# Battery_Characterizer.net
KiCad netlist of a schematic drawn in EAGLE
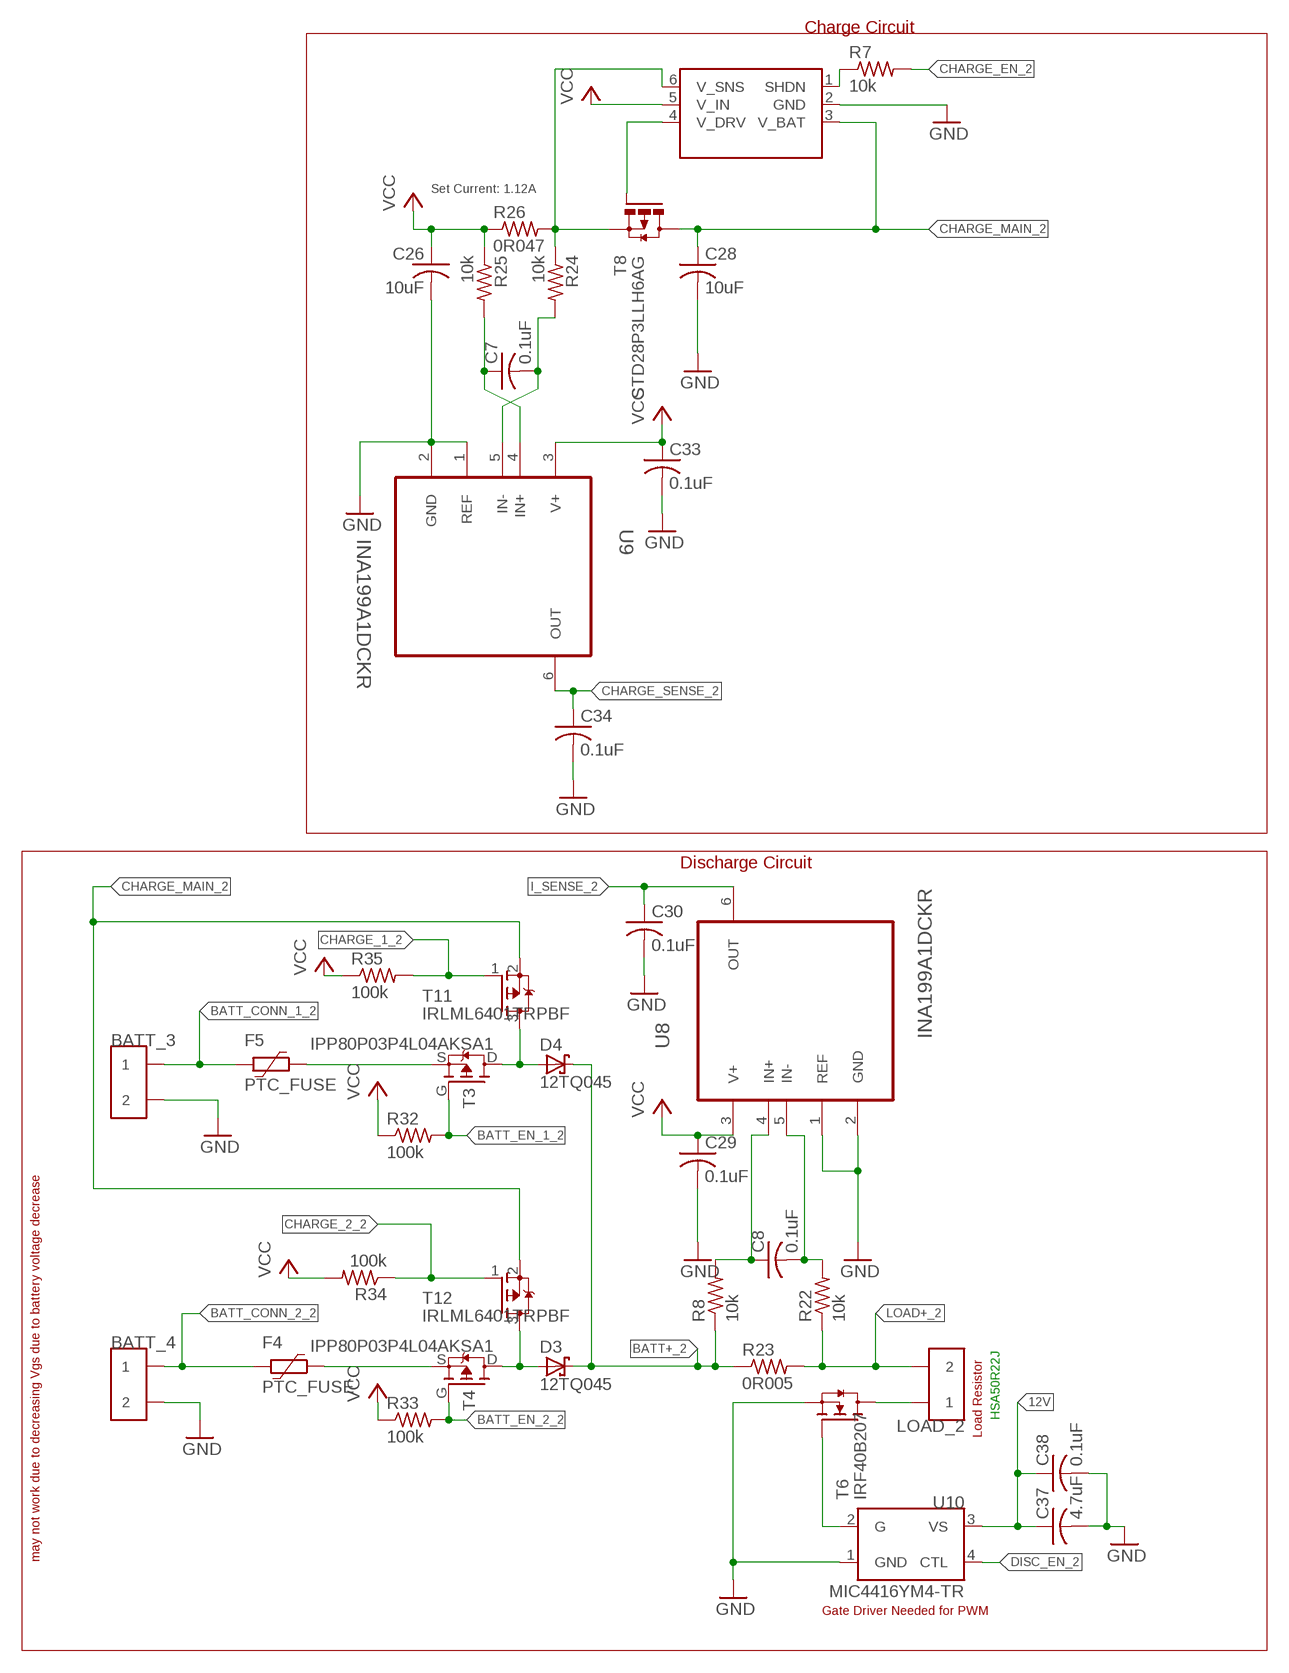
[diagram p0: schematic, sheet 1, part 1 of 2]
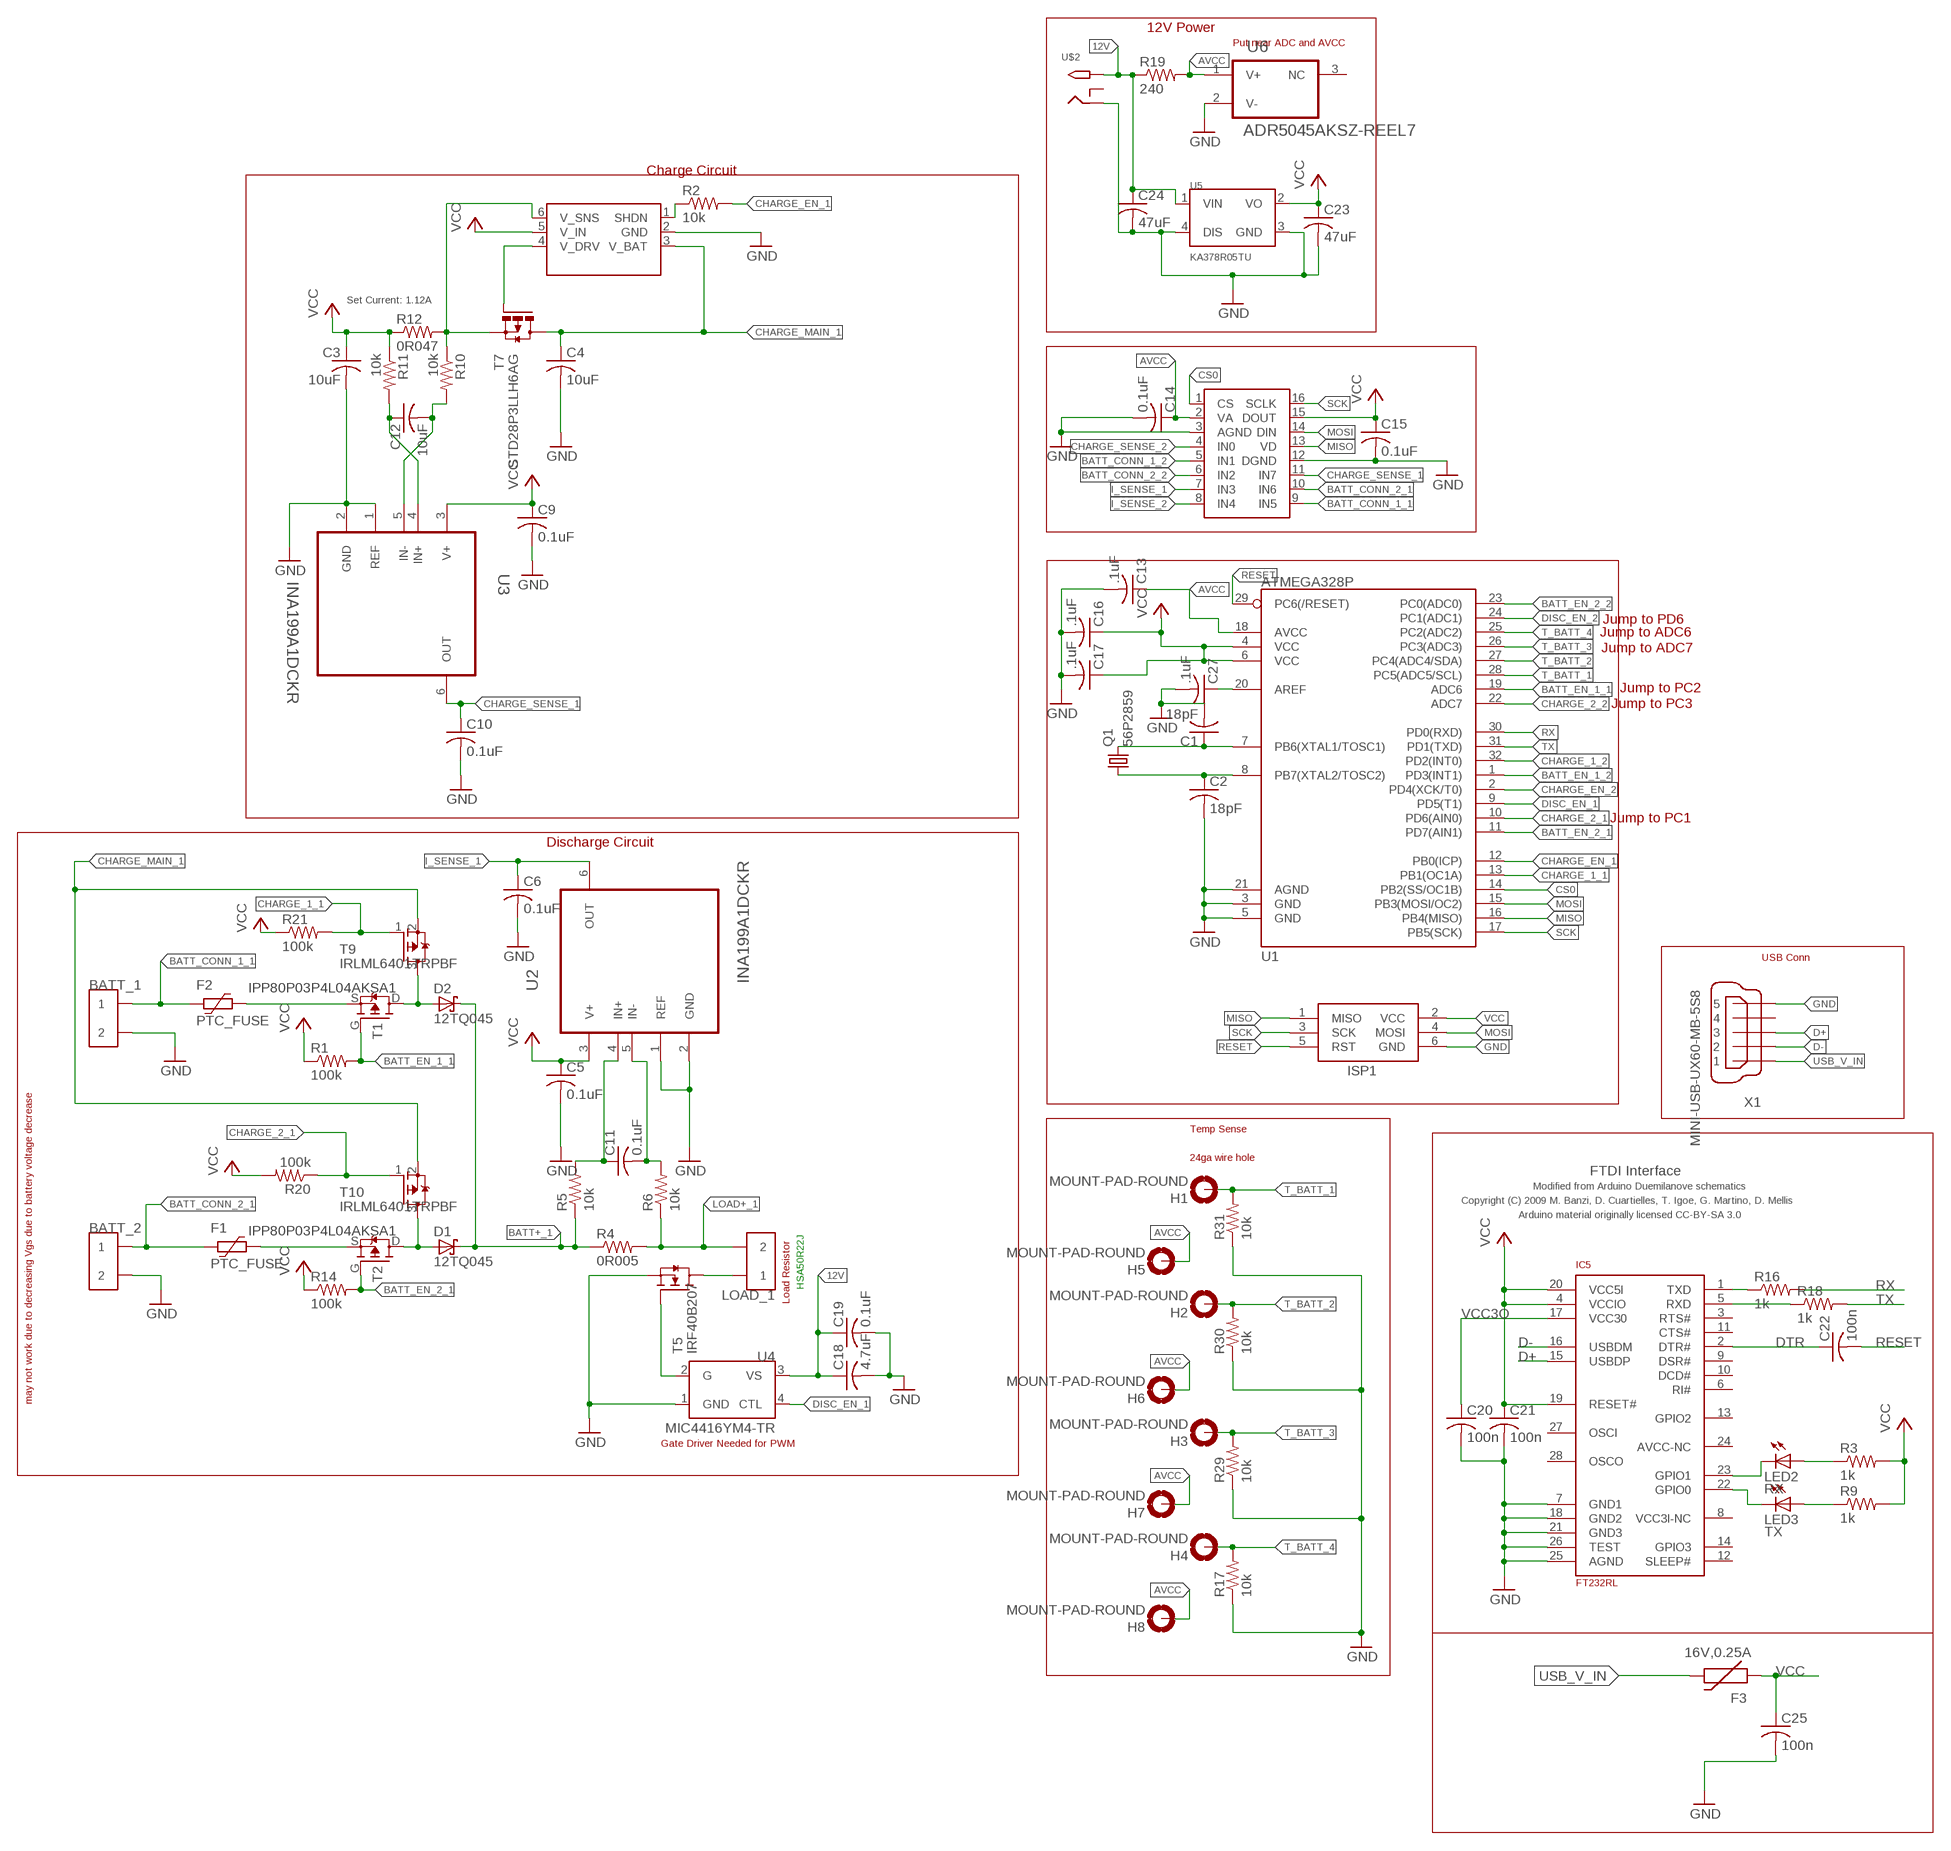
[diagram p1: schematic, sheet 1, part 2 of 2]

(export (version "E")
  (design (tool "Eeschema 10.0.6"))
  (components
    (comp (ref "BATT_1")
      (value "CONN_2")
      (footprint "eagle-import:CONNECTOR_2")
      (libsource (lib "eagle-import") (part "CONN_2"))
    )
    (comp (ref "BATT_2")
      (value "CONN_2")
      (footprint "eagle-import:CONNECTOR_2")
      (libsource (lib "eagle-import") (part "CONN_2"))
    )
    (comp (ref "BATT_3")
      (value "CONN_2")
      (footprint "eagle-import:CONNECTOR_2")
      (libsource (lib "eagle-import") (part "CONN_2"))
    )
    (comp (ref "BATT_4")
      (value "CONN_2")
      (footprint "eagle-import:CONNECTOR_2")
      (libsource (lib "eagle-import") (part "CONN_2"))
    )
    (comp (ref "C1")
      (value "18pF")
      (footprint "eagle-import:C0805")
      (libsource (lib "eagle-import") (part "C-USC0805"))
    )
    (comp (ref "C2")
      (value "18pF")
      (footprint "eagle-import:C0805")
      (libsource (lib "eagle-import") (part "C-USC0805"))
    )
    (comp (ref "C3")
      (value "10uF")
      (footprint "eagle-import:C0603")
      (libsource (lib "eagle-import") (part "C-USC0603"))
    )
    (comp (ref "C4")
      (value "10uF")
      (footprint "eagle-import:C0603")
      (libsource (lib "eagle-import") (part "C-USC0603"))
    )
    (comp (ref "C5")
      (value "0.1uF")
      (footprint "eagle-import:C0603")
      (libsource (lib "eagle-import") (part "C-USC0603"))
    )
    (comp (ref "C6")
      (value "0.1uF")
      (footprint "eagle-import:C0603")
      (libsource (lib "eagle-import") (part "C-USC0603"))
    )
    (comp (ref "C7")
      (value "0.1uF")
      (footprint "eagle-import:C0603")
      (libsource (lib "eagle-import") (part "C-USC0603"))
    )
    (comp (ref "C8")
      (value "0.1uF")
      (footprint "eagle-import:C0603")
      (libsource (lib "eagle-import") (part "C-USC0603"))
    )
    (comp (ref "C9")
      (value "0.1uF")
      (footprint "eagle-import:C0603")
      (libsource (lib "eagle-import") (part "C-USC0603"))
    )
    (comp (ref "C10")
      (value "0.1uF")
      (footprint "eagle-import:C0603")
      (libsource (lib "eagle-import") (part "C-USC0603"))
    )
    (comp (ref "C11")
      (value "0.1uF")
      (footprint "eagle-import:C0603")
      (libsource (lib "eagle-import") (part "C-USC0603"))
    )
    (comp (ref "C12")
      (value "10uF")
      (footprint "eagle-import:C0603")
      (libsource (lib "eagle-import") (part "C-USC0603"))
    )
    (comp (ref "C13")
      (value ".1uF")
      (footprint "eagle-import:C0603")
      (libsource (lib "eagle-import") (part "C-USC0603"))
    )
    (comp (ref "C14")
      (value "0.1uF")
      (footprint "eagle-import:C0603")
      (libsource (lib "eagle-import") (part "C-USC0603"))
    )
    (comp (ref "C15")
      (value "0.1uF")
      (footprint "eagle-import:C0603")
      (libsource (lib "eagle-import") (part "C-USC0603"))
    )
    (comp (ref "C16")
      (value ".1uF")
      (footprint "eagle-import:C0603")
      (libsource (lib "eagle-import") (part "C-USC0603"))
    )
    (comp (ref "C17")
      (value ".1uF")
      (footprint "eagle-import:C0603")
      (libsource (lib "eagle-import") (part "C-USC0603"))
    )
    (comp (ref "C18")
      (value "4.7uF")
      (footprint "eagle-import:C0805")
      (libsource (lib "eagle-import") (part "C-USC0805"))
    )
    (comp (ref "C19")
      (value "0.1uF")
      (footprint "eagle-import:C0603")
      (libsource (lib "eagle-import") (part "C-USC0603"))
    )
    (comp (ref "C20")
      (value "100n")
      (footprint "eagle-import:C0805")
      (libsource (lib "eagle-import") (part "C-USC0805"))
    )
    (comp (ref "C21")
      (value "100n")
      (footprint "eagle-import:C0805")
      (libsource (lib "eagle-import") (part "C-USC0805"))
    )
    (comp (ref "C22")
      (value "100n")
      (footprint "eagle-import:C0805")
      (libsource (lib "eagle-import") (part "C-USC0805"))
    )
    (comp (ref "C23")
      (value "47uF")
      (footprint "eagle-import:C0805")
      (libsource (lib "eagle-import") (part "resistor_C-USC0805"))
    )
    (comp (ref "C24")
      (value "47uF")
      (footprint "eagle-import:C0805")
      (libsource (lib "eagle-import") (part "C-USC0805"))
    )
    (comp (ref "C25")
      (value "100n")
      (footprint "eagle-import:C0805")
      (libsource (lib "eagle-import") (part "C-USC0805"))
    )
    (comp (ref "C26")
      (value "10uF")
      (footprint "eagle-import:C0603")
      (libsource (lib "eagle-import") (part "C-USC0603"))
    )
    (comp (ref "C27")
      (value ".1uF")
      (footprint "eagle-import:C0603")
      (libsource (lib "eagle-import") (part "C-USC0603"))
    )
    (comp (ref "C28")
      (value "10uF")
      (footprint "eagle-import:C0603")
      (libsource (lib "eagle-import") (part "C-USC0603"))
    )
    (comp (ref "C29")
      (value "0.1uF")
      (footprint "eagle-import:C0603")
      (libsource (lib "eagle-import") (part "C-USC0603"))
    )
    (comp (ref "C30")
      (value "0.1uF")
      (footprint "eagle-import:C0603")
      (libsource (lib "eagle-import") (part "C-USC0603"))
    )
    (comp (ref "C33")
      (value "0.1uF")
      (footprint "eagle-import:C0603")
      (libsource (lib "eagle-import") (part "C-USC0603"))
    )
    (comp (ref "C34")
      (value "0.1uF")
      (footprint "eagle-import:C0603")
      (libsource (lib "eagle-import") (part "C-USC0603"))
    )
    (comp (ref "C37")
      (value "4.7uF")
      (footprint "eagle-import:C0805")
      (libsource (lib "eagle-import") (part "C-USC0805"))
    )
    (comp (ref "C38")
      (value "0.1uF")
      (footprint "eagle-import:C0603")
      (libsource (lib "eagle-import") (part "C-USC0603"))
    )
    (comp (ref "D1")
      (value "12TQ045")
      (footprint "eagle-import:TO220-2")
      (libsource (lib "eagle-import") (part "12TQ045"))
    )
    (comp (ref "D2")
      (value "12TQ045")
      (footprint "eagle-import:TO220-2")
      (libsource (lib "eagle-import") (part "12TQ045"))
    )
    (comp (ref "D3")
      (value "12TQ045")
      (footprint "eagle-import:TO220-2")
      (libsource (lib "eagle-import") (part "12TQ045"))
    )
    (comp (ref "D4")
      (value "12TQ045")
      (footprint "eagle-import:TO220-2")
      (libsource (lib "eagle-import") (part "12TQ045"))
    )
    (comp (ref "F1")
      (value "PTC_FUSE")
      (footprint "eagle-import:RGEF1100")
      (libsource (lib "eagle-import") (part "PTC_FUSE"))
    )
    (comp (ref "F2")
      (value "PTC_FUSE")
      (footprint "eagle-import:RGEF1100")
      (libsource (lib "eagle-import") (part "PTC_FUSE"))
    )
    (comp (ref "F3")
      (value "16V,0.25A")
      (footprint "eagle-import:PTC-1206")
      (libsource (lib "eagle-import") (part "PTCSMD"))
    )
    (comp (ref "F4")
      (value "PTC_FUSE")
      (footprint "eagle-import:RGEF1100")
      (libsource (lib "eagle-import") (part "PTC_FUSE"))
    )
    (comp (ref "F5")
      (value "PTC_FUSE")
      (footprint "eagle-import:RGEF1100")
      (libsource (lib "eagle-import") (part "PTC_FUSE"))
    )
    (comp (ref "H1")
      (value "MOUNT-PAD-ROUND")
      (footprint "eagle-import:032-PAD")
      (libsource (lib "eagle-import") (part "MOUNT-PAD-ROUND"))
    )
    (comp (ref "H2")
      (value "MOUNT-PAD-ROUND")
      (footprint "eagle-import:032-PAD")
      (libsource (lib "eagle-import") (part "MOUNT-PAD-ROUND"))
    )
    (comp (ref "H3")
      (value "MOUNT-PAD-ROUND")
      (footprint "eagle-import:032-PAD")
      (libsource (lib "eagle-import") (part "MOUNT-PAD-ROUND"))
    )
    (comp (ref "H4")
      (value "MOUNT-PAD-ROUND")
      (footprint "eagle-import:032-PAD")
      (libsource (lib "eagle-import") (part "MOUNT-PAD-ROUND"))
    )
    (comp (ref "H5")
      (value "MOUNT-PAD-ROUND")
      (footprint "eagle-import:032-PAD")
      (libsource (lib "eagle-import") (part "MOUNT-PAD-ROUND"))
    )
    (comp (ref "H6")
      (value "MOUNT-PAD-ROUND")
      (footprint "eagle-import:032-PAD")
      (libsource (lib "eagle-import") (part "MOUNT-PAD-ROUND"))
    )
    (comp (ref "H7")
      (value "MOUNT-PAD-ROUND")
      (footprint "eagle-import:032-PAD")
      (libsource (lib "eagle-import") (part "MOUNT-PAD-ROUND"))
    )
    (comp (ref "H8")
      (value "MOUNT-PAD-ROUND")
      (footprint "eagle-import:032-PAD")
      (libsource (lib "eagle-import") (part "MOUNT-PAD-ROUND"))
    )
    (comp (ref "IC5")
      (value "FT232RL")
      (footprint "eagle-import:SSOP28")
      (libsource (lib "eagle-import") (part "FT232RL"))
    )
    (comp (ref "ISP1")
      (value "AVRISP-6")
      (footprint "eagle-import:AVRISP")
      (libsource (lib "eagle-import") (part "AVRISP-6"))
    )
    (comp (ref "LED2")
      (value "RX")
      (footprint "eagle-import:CHIPLED_0805")
      (libsource (lib "eagle-import") (part "LEDCHIPLED_0805"))
    )
    (comp (ref "LED3")
      (value "TX")
      (footprint "eagle-import:CHIPLED_0805")
      (libsource (lib "eagle-import") (part "LEDCHIPLED_0805"))
    )
    (comp (ref "LOAD_1")
      (value "CONN_2")
      (footprint "eagle-import:CONNECTOR_2")
      (libsource (lib "eagle-import") (part "CONN_2"))
    )
    (comp (ref "LOAD_2")
      (value "CONN_2")
      (footprint "eagle-import:CONNECTOR_2")
      (libsource (lib "eagle-import") (part "CONN_2"))
    )
    (comp (ref "PC1")
      (value "MCP73826")
      (footprint "eagle-import:SOT23-6")
      (libsource (lib "eagle-import") (part "MCP73826"))
    )
    (comp (ref "PC2")
      (value "MCP73826")
      (footprint "eagle-import:SOT23-6")
      (libsource (lib "eagle-import") (part "MCP73826"))
    )
    (comp (ref "Q1")
      (value "56P2859")
      (footprint "eagle-import:HC49UP")
      (libsource (lib "eagle-import") (part "CRYSTALSMD"))
    )
    (comp (ref "R1")
      (value "100k")
      (footprint "eagle-import:M0805")
      (libsource (lib "eagle-import") (part "R-US_M0805"))
    )
    (comp (ref "R2")
      (value "10k")
      (footprint "eagle-import:R0603")
      (libsource (lib "eagle-import") (part "resistor_R-US_R0603"))
    )
    (comp (ref "R3")
      (value "1k")
      (footprint "eagle-import:R0805")
      (libsource (lib "eagle-import") (part "R-US_R0805"))
    )
    (comp (ref "R4")
      (value "0R005")
      (footprint "eagle-import:R-3637")
      (libsource (lib "eagle-import") (part "WSL3637"))
    )
    (comp (ref "R5")
      (value "10k")
      (footprint "eagle-import:R0603")
      (libsource (lib "eagle-import") (part "resistor_R-US_R0603"))
    )
    (comp (ref "R6")
      (value "10k")
      (footprint "eagle-import:R0603")
      (libsource (lib "eagle-import") (part "resistor_R-US_R0603"))
    )
    (comp (ref "R7")
      (value "10k")
      (footprint "eagle-import:R0603")
      (libsource (lib "eagle-import") (part "resistor_R-US_R0603"))
    )
    (comp (ref "R8")
      (value "10k")
      (footprint "eagle-import:R0603")
      (libsource (lib "eagle-import") (part "resistor_R-US_R0603"))
    )
    (comp (ref "R9")
      (value "1k")
      (footprint "eagle-import:R0805")
      (libsource (lib "eagle-import") (part "R-US_R0805"))
    )
    (comp (ref "R10")
      (value "10k")
      (footprint "eagle-import:R0603")
      (libsource (lib "eagle-import") (part "resistor_R-US_R0603"))
    )
    (comp (ref "R11")
      (value "10k")
      (footprint "eagle-import:R0603")
      (libsource (lib "eagle-import") (part "resistor_R-US_R0603"))
    )
    (comp (ref "R12")
      (value "0R047")
      (footprint "eagle-import:M1206")
      (libsource (lib "eagle-import") (part "resistor_R-US_M1206"))
    )
    (comp (ref "R14")
      (value "100k")
      (footprint "eagle-import:M0805")
      (libsource (lib "eagle-import") (part "R-US_M0805"))
    )
    (comp (ref "R16")
      (value "1k")
      (footprint "eagle-import:R0805")
      (libsource (lib "eagle-import") (part "R-US_R0805"))
    )
    (comp (ref "R17")
      (value "10k")
      (footprint "eagle-import:R0603")
      (libsource (lib "eagle-import") (part "resistor_R-US_R0603"))
    )
    (comp (ref "R18")
      (value "1k")
      (footprint "eagle-import:R0805")
      (libsource (lib "eagle-import") (part "R-US_R0805"))
    )
    (comp (ref "R19")
      (value "240")
      (footprint "eagle-import:R0603")
      (libsource (lib "eagle-import") (part "resistor_R-US_R0603"))
    )
    (comp (ref "R20")
      (value "100k")
      (footprint "eagle-import:M0805")
      (libsource (lib "eagle-import") (part "R-US_M0805"))
    )
    (comp (ref "R21")
      (value "100k")
      (footprint "eagle-import:M0805")
      (libsource (lib "eagle-import") (part "R-US_M0805"))
    )
    (comp (ref "R22")
      (value "10k")
      (footprint "eagle-import:R0603")
      (libsource (lib "eagle-import") (part "resistor_R-US_R0603"))
    )
    (comp (ref "R23")
      (value "0R005")
      (footprint "eagle-import:R-3637")
      (libsource (lib "eagle-import") (part "WSL3637"))
    )
    (comp (ref "R24")
      (value "10k")
      (footprint "eagle-import:R0603")
      (libsource (lib "eagle-import") (part "resistor_R-US_R0603"))
    )
    (comp (ref "R25")
      (value "10k")
      (footprint "eagle-import:R0603")
      (libsource (lib "eagle-import") (part "resistor_R-US_R0603"))
    )
    (comp (ref "R26")
      (value "0R047")
      (footprint "eagle-import:M1206")
      (libsource (lib "eagle-import") (part "resistor_R-US_M1206"))
    )
    (comp (ref "R29")
      (value "10k")
      (footprint "eagle-import:R0603")
      (libsource (lib "eagle-import") (part "resistor_R-US_R0603"))
    )
    (comp (ref "R30")
      (value "10k")
      (footprint "eagle-import:R0603")
      (libsource (lib "eagle-import") (part "resistor_R-US_R0603"))
    )
    (comp (ref "R31")
      (value "10k")
      (footprint "eagle-import:R0603")
      (libsource (lib "eagle-import") (part "resistor_R-US_R0603"))
    )
    (comp (ref "R32")
      (value "100k")
      (footprint "eagle-import:M0805")
      (libsource (lib "eagle-import") (part "R-US_M0805"))
    )
    (comp (ref "R33")
      (value "100k")
      (footprint "eagle-import:M0805")
      (libsource (lib "eagle-import") (part "R-US_M0805"))
    )
    (comp (ref "R34")
      (value "100k")
      (footprint "eagle-import:M0805")
      (libsource (lib "eagle-import") (part "R-US_M0805"))
    )
    (comp (ref "R35")
      (value "100k")
      (footprint "eagle-import:M0805")
      (libsource (lib "eagle-import") (part "R-US_M0805"))
    )
    (comp (ref "T1")
      (value "IPP80P03P4L04AKSA1")
      (footprint "eagle-import:TO220-3")
      (libsource (lib "eagle-import") (part "IPP80P03P4L04AKSA1"))
    )
    (comp (ref "T2")
      (value "IPP80P03P4L04AKSA1")
      (footprint "eagle-import:TO220-3")
      (libsource (lib "eagle-import") (part "IPP80P03P4L04AKSA1"))
    )
    (comp (ref "T3")
      (value "IPP80P03P4L04AKSA1")
      (footprint "eagle-import:TO220-3")
      (libsource (lib "eagle-import") (part "IPP80P03P4L04AKSA1"))
    )
    (comp (ref "T4")
      (value "IPP80P03P4L04AKSA1")
      (footprint "eagle-import:TO220-3")
      (libsource (lib "eagle-import") (part "IPP80P03P4L04AKSA1"))
    )
    (comp (ref "T5")
      (value "IRF40B207")
      (footprint "eagle-import:TO220-3")
      (libsource (lib "eagle-import") (part "IRF40B207"))
    )
    (comp (ref "T6")
      (value "IRF40B207")
      (footprint "eagle-import:TO220-3")
      (libsource (lib "eagle-import") (part "IRF40B207"))
    )
    (comp (ref "T7")
      (value "STD28P3LLH6AG")
      (footprint "eagle-import:D2-PAK")
      (libsource (lib "eagle-import") (part "STD28P3LLH6AG"))
    )
    (comp (ref "T8")
      (value "STD28P3LLH6AG")
      (footprint "eagle-import:D2-PAK")
      (libsource (lib "eagle-import") (part "STD28P3LLH6AG"))
    )
    (comp (ref "T9")
      (value "IRLML6401TRPBF")
      (footprint "eagle-import:SOT95P237X112-3N")
      (libsource (lib "eagle-import") (part "IRLML6401TRPBF"))
    )
    (comp (ref "T10")
      (value "IRLML6401TRPBF")
      (footprint "eagle-import:SOT95P237X112-3N")
      (libsource (lib "eagle-import") (part "IRLML6401TRPBF"))
    )
    (comp (ref "T11")
      (value "IRLML6401TRPBF")
      (footprint "eagle-import:SOT95P237X112-3N")
      (libsource (lib "eagle-import") (part "IRLML6401TRPBF"))
    )
    (comp (ref "T12")
      (value "IRLML6401TRPBF")
      (footprint "eagle-import:SOT95P237X112-3N")
      (libsource (lib "eagle-import") (part "IRLML6401TRPBF"))
    )
    (comp (ref "U$2")
      (value "2.1MMJACKTHM")
      (footprint "eagle-import:PJ-102A")
      (libsource (lib "eagle-import") (part "2.1MMJACKTHM"))
    )
    (comp (ref "U$7")
      (value "ADC128S022CIMTX/NOPB")
      (footprint "eagle-import:TSSOP16")
      (libsource (lib "eagle-import") (part "ADC128S022CIMTX/NOPB"))
    )
    (comp (ref "U1")
      (value "ATMEGA328P")
      (footprint "eagle-import:TQFP32-08")
      (libsource (lib "eagle-import") (part "ATMEGA328_SMT"))
    )
    (comp (ref "U2")
      (value "INA199A1DCKR")
      (footprint "eagle-import:SOT65P210X110-6N")
      (libsource (lib "eagle-import") (part "INA199A1DCKR"))
    )
    (comp (ref "U3")
      (value "INA199A1DCKR")
      (footprint "eagle-import:SOT65P210X110-6N")
      (libsource (lib "eagle-import") (part "INA199A1DCKR"))
    )
    (comp (ref "U4")
      (value "MIC4416YM4-TR")
      (footprint "eagle-import:4-SOT_143")
      (libsource (lib "eagle-import") (part "MIC4416YM4-TR"))
    )
    (comp (ref "U5")
      (value "KA378R05TU")
      (footprint "eagle-import:TO-220-4")
      (libsource (lib "eagle-import") (part "KA378R05TU"))
    )
    (comp (ref "U6")
      (value "ADR5045AKSZ-REEL7")
      (footprint "eagle-import:SOT95P237X112-3N")
      (fields (field (name "MPN") "ADR5041BRTZ-R2") (field (name "MPN_1") "ADR5045AKSZ-REEL7"))
      (libsource (lib "eagle-import") (part "ADR5041BRTZ-R2"))
    )
    (comp (ref "U8")
      (value "INA199A1DCKR")
      (footprint "eagle-import:SOT65P210X110-6N")
      (libsource (lib "eagle-import") (part "INA199A1DCKR"))
    )
    (comp (ref "U9")
      (value "INA199A1DCKR")
      (footprint "eagle-import:SOT65P210X110-6N")
      (libsource (lib "eagle-import") (part "INA199A1DCKR"))
    )
    (comp (ref "U10")
      (value "MIC4416YM4-TR")
      (footprint "eagle-import:4-SOT_143")
      (libsource (lib "eagle-import") (part "MIC4416YM4-TR"))
    )
    (comp (ref "X1")
      (value "MINI-USB-UX60-MB-5S8")
      (footprint "eagle-import:UX60-MB-5S8")
      (libsource (lib "eagle-import") (part "MINI-USB-UX60-MB-5S8"))
    )
  )
  (nets
    (net (code "1") (name "/DTR") (class "Default")
      (node (ref "C22") (pin "1") (pinfunction "1_1") (pintype "passive"))
      (node (ref "IC5") (pin "2") (pinfunction "DTR#_2") (pintype "output"))
    )
    (net (code "2") (name "/VCC3O") (class "Default")
      (node (ref "C20") (pin "1") (pinfunction "1_1") (pintype "passive"))
      (node (ref "IC5") (pin "17") (pinfunction "VCC30_17") (pintype "power_in"))
    )
    (net (code "3") (name "12V") (class "Default")
      (node (ref "C18") (pin "1") (pinfunction "1_1") (pintype "passive"))
      (node (ref "C19") (pin "1") (pinfunction "1_1") (pintype "passive"))
      (node (ref "C24") (pin "1") (pinfunction "1_1") (pintype "passive"))
      (node (ref "C37") (pin "1") (pinfunction "1_1") (pintype "passive"))
      (node (ref "C38") (pin "1") (pinfunction "1_1") (pintype "passive"))
      (node (ref "R19") (pin "1") (pinfunction "1_1") (pintype "passive"))
      (node (ref "U$2") (pin "TIP") (pinfunction "TIP_TIP") (pintype "bidirectional"))
      (node (ref "U10") (pin "3") (pinfunction "VS_3") (pintype "bidirectional"))
      (node (ref "U4") (pin "3") (pinfunction "VS_3") (pintype "bidirectional"))
      (node (ref "U5") (pin "1") (pinfunction "VIN_1") (pintype "bidirectional"))
    )
    (net (code "4") (name "AVCC") (class "Default")
      (node (ref "C13") (pin "1") (pinfunction "1_1") (pintype "passive"))
      (node (ref "C14") (pin "1") (pinfunction "1_1") (pintype "passive"))
      (node (ref "H5") (pin "1") (pinfunction "MOUNT_1") (pintype "passive"))
      (node (ref "H6") (pin "1") (pinfunction "MOUNT_1") (pintype "passive"))
      (node (ref "H7") (pin "1") (pinfunction "MOUNT_1") (pintype "passive"))
      (node (ref "H8") (pin "1") (pinfunction "MOUNT_1") (pintype "passive"))
      (node (ref "R19") (pin "2") (pinfunction "2_2") (pintype "passive"))
      (node (ref "U$7") (pin "2") (pinfunction "VA_2") (pintype "bidirectional"))
      (node (ref "U1") (pin "18") (pinfunction "AVCC_18") (pintype "bidirectional"))
      (node (ref "U6") (pin "1") (pinfunction "V+_1") (pintype "power_in"))
    )
    (net (code "5") (name "BATT+_1") (class "Default")
      (node (ref "D1") (pin "C") (pinfunction "C_C") (pintype "passive"))
      (node (ref "D2") (pin "C") (pinfunction "C_C") (pintype "passive"))
      (node (ref "R4") (pin "1") (pinfunction "1_1") (pintype "passive"))
      (node (ref "R4") (pin "2") (pinfunction "1_2") (pintype "passive"))
      (node (ref "R5") (pin "1") (pinfunction "1_1") (pintype "passive"))
    )
    (net (code "6") (name "BATT+_2") (class "Default")
      (node (ref "D3") (pin "C") (pinfunction "C_C") (pintype "passive"))
      (node (ref "D4") (pin "C") (pinfunction "C_C") (pintype "passive"))
      (node (ref "R23") (pin "1") (pinfunction "1_1") (pintype "passive"))
      (node (ref "R23") (pin "2") (pinfunction "1_2") (pintype "passive"))
      (node (ref "R8") (pin "1") (pinfunction "1_1") (pintype "passive"))
    )
    (net (code "7") (name "BATT_CONN_1_1") (class "Default")
      (node (ref "BATT_1") (pin "1") (pinfunction "1_1") (pintype "bidirectional"))
      (node (ref "BATT_1") (pin "2") (pinfunction "1_2") (pintype "bidirectional"))
      (node (ref "F2") (pin "P$2") (pinfunction "2_P$2") (pintype "passive"))
      (node (ref "U$7") (pin "9") (pinfunction "IN5_9") (pintype "bidirectional"))
    )
    (net (code "8") (name "BATT_CONN_1_2") (class "Default")
      (node (ref "BATT_3") (pin "1") (pinfunction "1_1") (pintype "bidirectional"))
      (node (ref "BATT_3") (pin "2") (pinfunction "1_2") (pintype "bidirectional"))
      (node (ref "F5") (pin "P$2") (pinfunction "2_P$2") (pintype "passive"))
      (node (ref "U$7") (pin "5") (pinfunction "IN1_5") (pintype "bidirectional"))
    )
    (net (code "9") (name "BATT_CONN_2_1") (class "Default")
      (node (ref "BATT_2") (pin "1") (pinfunction "1_1") (pintype "bidirectional"))
      (node (ref "BATT_2") (pin "2") (pinfunction "1_2") (pintype "bidirectional"))
      (node (ref "F1") (pin "P$2") (pinfunction "2_P$2") (pintype "passive"))
      (node (ref "U$7") (pin "10") (pinfunction "IN6_10") (pintype "bidirectional"))
    )
    (net (code "10") (name "BATT_CONN_2_2") (class "Default")
      (node (ref "BATT_4") (pin "1") (pinfunction "1_1") (pintype "bidirectional"))
      (node (ref "BATT_4") (pin "2") (pinfunction "1_2") (pintype "bidirectional"))
      (node (ref "F4") (pin "P$2") (pinfunction "2_P$2") (pintype "passive"))
      (node (ref "U$7") (pin "6") (pinfunction "IN2_6") (pintype "bidirectional"))
    )
    (net (code "11") (name "BATT_EN_1_1") (class "Default")
      (node (ref "R1") (pin "2") (pinfunction "2_2") (pintype "passive"))
      (node (ref "T1") (pin "G") (pinfunction "G_G") (pintype "passive"))
      (node (ref "U1") (pin "19") (pinfunction "ADC6_19") (pintype "bidirectional"))
    )
    (net (code "12") (name "BATT_EN_1_2") (class "Default")
      (node (ref "R32") (pin "2") (pinfunction "2_2") (pintype "passive"))
      (node (ref "T3") (pin "G") (pinfunction "G_G") (pintype "passive"))
      (node (ref "U1") (pin "1") (pinfunction "PD3(INT1)_1") (pintype "bidirectional"))
    )
    (net (code "13") (name "BATT_EN_2_1") (class "Default")
      (node (ref "R14") (pin "2") (pinfunction "2_2") (pintype "passive"))
      (node (ref "T2") (pin "G") (pinfunction "G_G") (pintype "passive"))
      (node (ref "U1") (pin "11") (pinfunction "PD7(AIN1)_11") (pintype "bidirectional"))
    )
    (net (code "14") (name "BATT_EN_2_2") (class "Default")
      (node (ref "R33") (pin "2") (pinfunction "2_2") (pintype "passive"))
      (node (ref "T4") (pin "G") (pinfunction "G_G") (pintype "passive"))
      (node (ref "U1") (pin "23") (pinfunction "PC0(ADC0)_23") (pintype "bidirectional"))
    )
    (net (code "15") (name "CHARGE_1_1") (class "Default")
      (node (ref "R21") (pin "2") (pinfunction "2_2") (pintype "passive"))
      (node (ref "T9") (pin "1") (pinfunction "G_1") (pintype "passive"))
      (node (ref "U1") (pin "13") (pinfunction "PB1(OC1A)_13") (pintype "bidirectional"))
    )
    (net (code "16") (name "CHARGE_1_2") (class "Default")
      (node (ref "R35") (pin "2") (pinfunction "2_2") (pintype "passive"))
      (node (ref "T11") (pin "1") (pinfunction "G_1") (pintype "passive"))
      (node (ref "U1") (pin "32") (pinfunction "PD2(INT0)_32") (pintype "bidirectional"))
    )
    (net (code "17") (name "CHARGE_2_1") (class "Default")
      (node (ref "R20") (pin "1") (pinfunction "1_1") (pintype "passive"))
      (node (ref "T10") (pin "1") (pinfunction "G_1") (pintype "passive"))
      (node (ref "U1") (pin "10") (pinfunction "PD6(AIN0)_10") (pintype "bidirectional"))
    )
    (net (code "18") (name "CHARGE_2_2") (class "Default")
      (node (ref "R34") (pin "1") (pinfunction "1_1") (pintype "passive"))
      (node (ref "T12") (pin "1") (pinfunction "G_1") (pintype "passive"))
      (node (ref "U1") (pin "22") (pinfunction "ADC7_22") (pintype "bidirectional"))
    )
    (net (code "19") (name "CHARGE_EN_1") (class "Default")
      (node (ref "R2") (pin "2") (pinfunction "2_2") (pintype "passive"))
      (node (ref "U1") (pin "12") (pinfunction "PB0(ICP)_12") (pintype "bidirectional"))
    )
    (net (code "20") (name "CHARGE_EN_2") (class "Default")
      (node (ref "R7") (pin "2") (pinfunction "2_2") (pintype "passive"))
      (node (ref "U1") (pin "2") (pinfunction "PD4(XCK/T0)_2") (pintype "bidirectional"))
    )
    (net (code "21") (name "CHARGE_MAIN_1") (class "Default")
      (node (ref "C4") (pin "1") (pinfunction "1_1") (pintype "passive"))
      (node (ref "PC1") (pin "3") (pinfunction "V_BAT_3") (pintype "bidirectional"))
      (node (ref "T10") (pin "2") (pinfunction "S_2") (pintype "passive"))
      (node (ref "T7") (pin "2") (pinfunction "D_2") (pintype "passive"))
      (node (ref "T7") (pin "P$1") (pinfunction "D_P$1") (pintype "passive"))
      (node (ref "T7") (pin "P$10") (pinfunction "D_P$10") (pintype "passive"))
      (node (ref "T7") (pin "P$11") (pinfunction "D_P$11") (pintype "passive"))
      (node (ref "T7") (pin "P$12") (pinfunction "D_P$12") (pintype "passive"))
      (node (ref "T7") (pin "P$13") (pinfunction "D_P$13") (pintype "passive"))
      (node (ref "T7") (pin "P$14") (pinfunction "D_P$14") (pintype "passive"))
      (node (ref "T7") (pin "P$15") (pinfunction "D_P$15") (pintype "passive"))
      (node (ref "T7") (pin "P$16") (pinfunction "D_P$16") (pintype "passive"))
      (node (ref "T7") (pin "P$17") (pinfunction "D_P$17") (pintype "passive"))
      (node (ref "T7") (pin "P$18") (pinfunction "D_P$18") (pintype "passive"))
      (node (ref "T7") (pin "P$19") (pinfunction "D_P$19") (pintype "passive"))
      (node (ref "T7") (pin "P$2") (pinfunction "D_P$2") (pintype "passive"))
      (node (ref "T7") (pin "P$20") (pinfunction "D_P$20") (pintype "passive"))
      (node (ref "T7") (pin "P$21") (pinfunction "D_P$21") (pintype "passive"))
      (node (ref "T7") (pin "P$22") (pinfunction "D_P$22") (pintype "passive"))
      (node (ref "T7") (pin "P$23") (pinfunction "D_P$23") (pintype "passive"))
      (node (ref "T7") (pin "P$24") (pinfunction "D_P$24") (pintype "passive"))
      (node (ref "T7") (pin "P$25") (pinfunction "D_P$25") (pintype "passive"))
      (node (ref "T7") (pin "P$26") (pinfunction "D_P$26") (pintype "passive"))
      (node (ref "T7") (pin "P$27") (pinfunction "D_P$27") (pintype "passive"))
      (node (ref "T7") (pin "P$28") (pinfunction "D_P$28") (pintype "passive"))
      (node (ref "T7") (pin "P$29") (pinfunction "D_P$29") (pintype "passive"))
      (node (ref "T7") (pin "P$3") (pinfunction "D_P$3") (pintype "passive"))
      (node (ref "T7") (pin "P$30") (pinfunction "D_P$30") (pintype "passive"))
      (node (ref "T7") (pin "P$4") (pinfunction "D_P$4") (pintype "passive"))
      (node (ref "T7") (pin "P$5") (pinfunction "D_P$5") (pintype "passive"))
      (node (ref "T7") (pin "P$6") (pinfunction "D_P$6") (pintype "passive"))
      (node (ref "T7") (pin "P$7") (pinfunction "D_P$7") (pintype "passive"))
      (node (ref "T7") (pin "P$8") (pinfunction "D_P$8") (pintype "passive"))
      (node (ref "T7") (pin "P$9") (pinfunction "D_P$9") (pintype "passive"))
      (node (ref "T9") (pin "2") (pinfunction "S_2") (pintype "passive"))
    )
    (net (code "22") (name "CHARGE_MAIN_2") (class "Default")
      (node (ref "C28") (pin "1") (pinfunction "1_1") (pintype "passive"))
      (node (ref "PC2") (pin "3") (pinfunction "V_BAT_3") (pintype "bidirectional"))
      (node (ref "T11") (pin "2") (pinfunction "S_2") (pintype "passive"))
      (node (ref "T12") (pin "2") (pinfunction "S_2") (pintype "passive"))
      (node (ref "T8") (pin "2") (pinfunction "D_2") (pintype "passive"))
      (node (ref "T8") (pin "P$1") (pinfunction "D_P$1") (pintype "passive"))
      (node (ref "T8") (pin "P$10") (pinfunction "D_P$10") (pintype "passive"))
      (node (ref "T8") (pin "P$11") (pinfunction "D_P$11") (pintype "passive"))
      (node (ref "T8") (pin "P$12") (pinfunction "D_P$12") (pintype "passive"))
      (node (ref "T8") (pin "P$13") (pinfunction "D_P$13") (pintype "passive"))
      (node (ref "T8") (pin "P$14") (pinfunction "D_P$14") (pintype "passive"))
      (node (ref "T8") (pin "P$15") (pinfunction "D_P$15") (pintype "passive"))
      (node (ref "T8") (pin "P$16") (pinfunction "D_P$16") (pintype "passive"))
      (node (ref "T8") (pin "P$17") (pinfunction "D_P$17") (pintype "passive"))
      (node (ref "T8") (pin "P$18") (pinfunction "D_P$18") (pintype "passive"))
      (node (ref "T8") (pin "P$19") (pinfunction "D_P$19") (pintype "passive"))
      (node (ref "T8") (pin "P$2") (pinfunction "D_P$2") (pintype "passive"))
      (node (ref "T8") (pin "P$20") (pinfunction "D_P$20") (pintype "passive"))
      (node (ref "T8") (pin "P$21") (pinfunction "D_P$21") (pintype "passive"))
      (node (ref "T8") (pin "P$22") (pinfunction "D_P$22") (pintype "passive"))
      (node (ref "T8") (pin "P$23") (pinfunction "D_P$23") (pintype "passive"))
      (node (ref "T8") (pin "P$24") (pinfunction "D_P$24") (pintype "passive"))
      (node (ref "T8") (pin "P$25") (pinfunction "D_P$25") (pintype "passive"))
      (node (ref "T8") (pin "P$26") (pinfunction "D_P$26") (pintype "passive"))
      (node (ref "T8") (pin "P$27") (pinfunction "D_P$27") (pintype "passive"))
      (node (ref "T8") (pin "P$28") (pinfunction "D_P$28") (pintype "passive"))
      (node (ref "T8") (pin "P$29") (pinfunction "D_P$29") (pintype "passive"))
      (node (ref "T8") (pin "P$3") (pinfunction "D_P$3") (pintype "passive"))
      (node (ref "T8") (pin "P$30") (pinfunction "D_P$30") (pintype "passive"))
      (node (ref "T8") (pin "P$4") (pinfunction "D_P$4") (pintype "passive"))
      (node (ref "T8") (pin "P$5") (pinfunction "D_P$5") (pintype "passive"))
      (node (ref "T8") (pin "P$6") (pinfunction "D_P$6") (pintype "passive"))
      (node (ref "T8") (pin "P$7") (pinfunction "D_P$7") (pintype "passive"))
      (node (ref "T8") (pin "P$8") (pinfunction "D_P$8") (pintype "passive"))
      (node (ref "T8") (pin "P$9") (pinfunction "D_P$9") (pintype "passive"))
    )
    (net (code "23") (name "CHARGE_SENSE_1") (class "Default")
      (node (ref "C10") (pin "1") (pinfunction "1_1") (pintype "passive"))
      (node (ref "U$7") (pin "11") (pinfunction "IN7_11") (pintype "bidirectional"))
      (node (ref "U3") (pin "6") (pinfunction "OUT_6") (pintype "output"))
    )
    (net (code "24") (name "CHARGE_SENSE_2") (class "Default")
      (node (ref "C34") (pin "1") (pinfunction "1_1") (pintype "passive"))
      (node (ref "U$7") (pin "4") (pinfunction "IN0_4") (pintype "bidirectional"))
      (node (ref "U9") (pin "6") (pinfunction "OUT_6") (pintype "output"))
    )
    (net (code "25") (name "CS0") (class "Default")
      (node (ref "U$7") (pin "1") (pinfunction "CS_1") (pintype "bidirectional"))
      (node (ref "U1") (pin "14") (pinfunction "PB2(SS/OC1B)_14") (pintype "bidirectional"))
    )
    (net (code "26") (name "D+") (class "Default")
      (node (ref "IC5") (pin "15") (pinfunction "USBDP_15") (pintype "bidirectional"))
      (node (ref "X1") (pin "3") (pinfunction "3_3") (pintype "input"))
    )
    (net (code "27") (name "D-") (class "Default")
      (node (ref "IC5") (pin "16") (pinfunction "USBDM_16") (pintype "bidirectional"))
      (node (ref "X1") (pin "2") (pinfunction "2_2") (pintype "input"))
    )
    (net (code "28") (name "DISC_EN_1") (class "Default")
      (node (ref "U1") (pin "9") (pinfunction "PD5(T1)_9") (pintype "bidirectional"))
      (node (ref "U4") (pin "4") (pinfunction "CTL_4") (pintype "bidirectional"))
    )
    (net (code "29") (name "DISC_EN_2") (class "Default")
      (node (ref "U1") (pin "24") (pinfunction "PC1(ADC1)_24") (pintype "bidirectional"))
      (node (ref "U10") (pin "4") (pinfunction "CTL_4") (pintype "bidirectional"))
    )
    (net (code "30") (name "GND") (class "Default")
      (node (ref "BATT_1") (pin "3") (pinfunction "2_3") (pintype "bidirectional"))
      (node (ref "BATT_1") (pin "4") (pinfunction "2_4") (pintype "bidirectional"))
      (node (ref "BATT_2") (pin "3") (pinfunction "2_3") (pintype "bidirectional"))
      (node (ref "BATT_2") (pin "4") (pinfunction "2_4") (pintype "bidirectional"))
      (node (ref "BATT_3") (pin "3") (pinfunction "2_3") (pintype "bidirectional"))
      (node (ref "BATT_3") (pin "4") (pinfunction "2_4") (pintype "bidirectional"))
      (node (ref "BATT_4") (pin "3") (pinfunction "2_3") (pintype "bidirectional"))
      (node (ref "BATT_4") (pin "4") (pinfunction "2_4") (pintype "bidirectional"))
      (node (ref "C1") (pin "2") (pinfunction "2_2") (pintype "passive"))
      (node (ref "C10") (pin "2") (pinfunction "2_2") (pintype "passive"))
      (node (ref "C13") (pin "2") (pinfunction "2_2") (pintype "passive"))
      (node (ref "C14") (pin "2") (pinfunction "2_2") (pintype "passive"))
      (node (ref "C15") (pin "2") (pinfunction "2_2") (pintype "passive"))
      (node (ref "C16") (pin "2") (pinfunction "2_2") (pintype "passive"))
      (node (ref "C17") (pin "2") (pinfunction "2_2") (pintype "passive"))
      (node (ref "C18") (pin "2") (pinfunction "2_2") (pintype "passive"))
      (node (ref "C19") (pin "2") (pinfunction "2_2") (pintype "passive"))
      (node (ref "C2") (pin "2") (pinfunction "2_2") (pintype "passive"))
      (node (ref "C20") (pin "2") (pinfunction "2_2") (pintype "passive"))
      (node (ref "C21") (pin "2") (pinfunction "2_2") (pintype "passive"))
      (node (ref "C23") (pin "2") (pinfunction "2_2") (pintype "passive"))
      (node (ref "C24") (pin "2") (pinfunction "2_2") (pintype "passive"))
      (node (ref "C25") (pin "2") (pinfunction "2_2") (pintype "passive"))
      (node (ref "C26") (pin "2") (pinfunction "2_2") (pintype "passive"))
      (node (ref "C27") (pin "2") (pinfunction "2_2") (pintype "passive"))
      (node (ref "C28") (pin "2") (pinfunction "2_2") (pintype "passive"))
      (node (ref "C29") (pin "2") (pinfunction "2_2") (pintype "passive"))
      (node (ref "C3") (pin "2") (pinfunction "2_2") (pintype "passive"))
      (node (ref "C30") (pin "2") (pinfunction "2_2") (pintype "passive"))
      (node (ref "C33") (pin "2") (pinfunction "2_2") (pintype "passive"))
      (node (ref "C34") (pin "2") (pinfunction "2_2") (pintype "passive"))
      (node (ref "C37") (pin "2") (pinfunction "2_2") (pintype "passive"))
      (node (ref "C38") (pin "2") (pinfunction "2_2") (pintype "passive"))
      (node (ref "C4") (pin "2") (pinfunction "2_2") (pintype "passive"))
      (node (ref "C5") (pin "2") (pinfunction "2_2") (pintype "passive"))
      (node (ref "C6") (pin "2") (pinfunction "2_2") (pintype "passive"))
      (node (ref "C9") (pin "2") (pinfunction "2_2") (pintype "passive"))
      (node (ref "IC5") (pin "18") (pinfunction "GND2_18") (pintype "power_in"))
      (node (ref "IC5") (pin "21") (pinfunction "GND3_21") (pintype "power_in"))
      (node (ref "IC5") (pin "25") (pinfunction "AGND_25") (pintype "power_in"))
      (node (ref "IC5") (pin "26") (pinfunction "TEST_26") (pintype "input"))
      (node (ref "IC5") (pin "7") (pinfunction "GND1_7") (pintype "power_in"))
      (node (ref "ISP1") (pin "6") (pinfunction "GND_6") (pintype "power_in"))
      (node (ref "PC1") (pin "2") (pinfunction "GND_2") (pintype "bidirectional"))
      (node (ref "PC2") (pin "2") (pinfunction "GND_2") (pintype "bidirectional"))
      (node (ref "R17") (pin "1") (pinfunction "1_1") (pintype "passive"))
      (node (ref "R29") (pin "1") (pinfunction "1_1") (pintype "passive"))
      (node (ref "R30") (pin "1") (pinfunction "1_1") (pintype "passive"))
      (node (ref "R31") (pin "1") (pinfunction "1_1") (pintype "passive"))
      (node (ref "T5") (pin "S") (pinfunction "S_S") (pintype "passive"))
      (node (ref "T6") (pin "S") (pinfunction "S_S") (pintype "passive"))
      (node (ref "U$2") (pin "RING") (pinfunction "RING_RING") (pintype "bidirectional"))
      (node (ref "U$7") (pin "12") (pinfunction "DGND_12") (pintype "bidirectional"))
      (node (ref "U$7") (pin "3") (pinfunction "AGND_3") (pintype "bidirectional"))
      (node (ref "U1") (pin "21") (pinfunction "AGND_21") (pintype "bidirectional"))
      (node (ref "U1") (pin "3") (pinfunction "GND_3") (pintype "bidirectional"))
      (node (ref "U1") (pin "5") (pinfunction "GND_5") (pintype "bidirectional"))
      (node (ref "U10") (pin "1") (pinfunction "GND_1") (pintype "bidirectional"))
      (node (ref "U2") (pin "1") (pinfunction "REF_1") (pintype "input"))
      (node (ref "U2") (pin "2") (pinfunction "GND_2") (pintype "passive"))
      (node (ref "U3") (pin "1") (pinfunction "REF_1") (pintype "input"))
      (node (ref "U3") (pin "2") (pinfunction "GND_2") (pintype "passive"))
      (node (ref "U4") (pin "1") (pinfunction "GND_1") (pintype "bidirectional"))
      (node (ref "U5") (pin "3") (pinfunction "GND_3") (pintype "bidirectional"))
      (node (ref "U5") (pin "4") (pinfunction "DIS_4") (pintype "bidirectional"))
      (node (ref "U6") (pin "2") (pinfunction "V-_2") (pintype "power_in"))
      (node (ref "U8") (pin "1") (pinfunction "REF_1") (pintype "input"))
      (node (ref "U8") (pin "2") (pinfunction "GND_2") (pintype "passive"))
      (node (ref "U9") (pin "1") (pinfunction "REF_1") (pintype "input"))
      (node (ref "U9") (pin "2") (pinfunction "GND_2") (pintype "passive"))
      (node (ref "X1") (pin "5") (pinfunction "5_5") (pintype "input"))
      (node (ref "X1") (pin "M1") (pinfunction "5_M1") (pintype "input"))
      (node (ref "X1") (pin "M2") (pinfunction "5_M2") (pintype "input"))
      (node (ref "X1") (pin "M3") (pinfunction "5_M3") (pintype "input"))
      (node (ref "X1") (pin "M4") (pinfunction "5_M4") (pintype "input"))
    )
    (net (code "31") (name "I_SENSE_1") (class "Default")
      (node (ref "C6") (pin "1") (pinfunction "1_1") (pintype "passive"))
      (node (ref "U$7") (pin "7") (pinfunction "IN3_7") (pintype "bidirectional"))
      (node (ref "U2") (pin "6") (pinfunction "OUT_6") (pintype "output"))
    )
    (net (code "32") (name "I_SENSE_2") (class "Default")
      (node (ref "C30") (pin "1") (pinfunction "1_1") (pintype "passive"))
      (node (ref "U$7") (pin "8") (pinfunction "IN4_8") (pintype "bidirectional"))
      (node (ref "U8") (pin "6") (pinfunction "OUT_6") (pintype "output"))
    )
    (net (code "33") (name "LOAD+_1") (class "Default")
      (node (ref "LOAD_1") (pin "3") (pinfunction "2_3") (pintype "bidirectional"))
      (node (ref "LOAD_1") (pin "4") (pinfunction "2_4") (pintype "bidirectional"))
      (node (ref "R4") (pin "3") (pinfunction "2_3") (pintype "passive"))
      (node (ref "R4") (pin "4") (pinfunction "2_4") (pintype "passive"))
      (node (ref "R6") (pin "1") (pinfunction "1_1") (pintype "passive"))
    )
    (net (code "34") (name "LOAD+_2") (class "Default")
      (node (ref "LOAD_2") (pin "3") (pinfunction "2_3") (pintype "bidirectional"))
      (node (ref "LOAD_2") (pin "4") (pinfunction "2_4") (pintype "bidirectional"))
      (node (ref "R22") (pin "1") (pinfunction "1_1") (pintype "passive"))
      (node (ref "R23") (pin "3") (pinfunction "2_3") (pintype "passive"))
      (node (ref "R23") (pin "4") (pinfunction "2_4") (pintype "passive"))
    )
    (net (code "35") (name "MISO") (class "Default")
      (node (ref "ISP1") (pin "1") (pinfunction "MISO_1") (pintype "input"))
      (node (ref "U$7") (pin "13") (pinfunction "VD_13") (pintype "bidirectional"))
      (node (ref "U1") (pin "16") (pinfunction "PB4(MISO)_16") (pintype "bidirectional"))
    )
    (net (code "36") (name "MOSI") (class "Default")
      (node (ref "ISP1") (pin "4") (pinfunction "MOSI_4") (pintype "output"))
      (node (ref "U$7") (pin "14") (pinfunction "DIN_14") (pintype "bidirectional"))
      (node (ref "U1") (pin "15") (pinfunction "PB3(MOSI/OC2)_15") (pintype "bidirectional"))
    )
    (net (code "37") (name "Net-(F1-1)") (class "Default")
      (node (ref "F1") (pin "P$1") (pinfunction "1_P$1") (pintype "passive"))
      (node (ref "T2") (pin "S") (pinfunction "S_S") (pintype "passive"))
    )
    (net (code "38") (name "Net-(F2-1)") (class "Default")
      (node (ref "F2") (pin "P$1") (pinfunction "1_P$1") (pintype "passive"))
      (node (ref "T1") (pin "S") (pinfunction "S_S") (pintype "passive"))
    )
    (net (code "39") (name "Net-(F4-1)") (class "Default")
      (node (ref "F4") (pin "P$1") (pinfunction "1_P$1") (pintype "passive"))
      (node (ref "T4") (pin "S") (pinfunction "S_S") (pintype "passive"))
    )
    (net (code "40") (name "Net-(F5-1)") (class "Default")
      (node (ref "F5") (pin "P$1") (pinfunction "1_P$1") (pintype "passive"))
      (node (ref "T3") (pin "S") (pinfunction "S_S") (pintype "passive"))
    )
    (net (code "41") (name "Net-(IC5-GPIO0)") (class "Default")
      (node (ref "IC5") (pin "22") (pinfunction "GPIO0_22") (pintype "output"))
      (node (ref "LED3") (pin "C") (pinfunction "C_C") (pintype "passive"))
    )
    (net (code "42") (name "Net-(IC5-GPIO1)") (class "Default")
      (node (ref "IC5") (pin "23") (pinfunction "GPIO1_23") (pintype "output"))
      (node (ref "LED2") (pin "C") (pinfunction "C_C") (pintype "passive"))
    )
    (net (code "43") (name "Net-(IC5-RXD)") (class "Default")
      (node (ref "IC5") (pin "5") (pinfunction "RXD_5") (pintype "input"))
      (node (ref "R18") (pin "1") (pinfunction "1_1") (pintype "passive"))
    )
    (net (code "44") (name "Net-(IC5-TXD)") (class "Default")
      (node (ref "IC5") (pin "1") (pinfunction "TXD_1") (pintype "output"))
      (node (ref "R16") (pin "1") (pinfunction "1_1") (pintype "passive"))
    )
    (net (code "45") (name "Net-(LED2-PadA)") (class "Default")
      (node (ref "LED2") (pin "A") (pinfunction "A_A") (pintype "passive"))
      (node (ref "R3") (pin "1") (pinfunction "1_1") (pintype "passive"))
    )
    (net (code "46") (name "Net-(LED3-PadA)") (class "Default")
      (node (ref "LED3") (pin "A") (pinfunction "A_A") (pintype "passive"))
      (node (ref "R9") (pin "1") (pinfunction "1_1") (pintype "passive"))
    )
    (net (code "47") (name "Net-(LOAD_1-1-Pad2)") (class "Default")
      (node (ref "LOAD_1") (pin "1") (pinfunction "1_1") (pintype "bidirectional"))
      (node (ref "LOAD_1") (pin "2") (pinfunction "1_2") (pintype "bidirectional"))
      (node (ref "T5") (pin "D") (pinfunction "D_D") (pintype "passive"))
    )
    (net (code "48") (name "Net-(LOAD_2-1-Pad2)") (class "Default")
      (node (ref "LOAD_2") (pin "1") (pinfunction "1_1") (pintype "bidirectional"))
      (node (ref "LOAD_2") (pin "2") (pinfunction "1_2") (pintype "bidirectional"))
      (node (ref "T6") (pin "D") (pinfunction "D_D") (pintype "passive"))
    )
    (net (code "49") (name "Net-(PC1-SHDN)") (class "Default")
      (node (ref "PC1") (pin "1") (pinfunction "SHDN_1") (pintype "bidirectional"))
      (node (ref "R2") (pin "1") (pinfunction "1_1") (pintype "passive"))
    )
    (net (code "50") (name "Net-(PC1-V_DRV)") (class "Default")
      (node (ref "PC1") (pin "4") (pinfunction "V_DRV_4") (pintype "bidirectional"))
      (node (ref "T7") (pin "1") (pinfunction "G_1") (pintype "passive"))
    )
    (net (code "51") (name "Net-(PC1-V_SNS)") (class "Default")
      (node (ref "PC1") (pin "6") (pinfunction "V_SNS_6") (pintype "bidirectional"))
      (node (ref "R10") (pin "1") (pinfunction "1_1") (pintype "passive"))
      (node (ref "R12") (pin "2") (pinfunction "2_2") (pintype "passive"))
      (node (ref "T7") (pin "3") (pinfunction "S_3") (pintype "passive"))
    )
    (net (code "52") (name "Net-(PC2-SHDN)") (class "Default")
      (node (ref "PC2") (pin "1") (pinfunction "SHDN_1") (pintype "bidirectional"))
      (node (ref "R7") (pin "1") (pinfunction "1_1") (pintype "passive"))
    )
    (net (code "53") (name "Net-(PC2-V_DRV)") (class "Default")
      (node (ref "PC2") (pin "4") (pinfunction "V_DRV_4") (pintype "bidirectional"))
      (node (ref "T8") (pin "1") (pinfunction "G_1") (pintype "passive"))
    )
    (net (code "54") (name "Net-(PC2-V_SNS)") (class "Default")
      (node (ref "PC2") (pin "6") (pinfunction "V_SNS_6") (pintype "bidirectional"))
      (node (ref "R24") (pin "1") (pinfunction "1_1") (pintype "passive"))
      (node (ref "R26") (pin "2") (pinfunction "2_2") (pintype "passive"))
      (node (ref "T8") (pin "3") (pinfunction "S_3") (pintype "passive"))
    )
    (net (code "55") (name "Net-(T9-D)") (class "Default")
      (node (ref "D2") (pin "A") (pinfunction "A_A") (pintype "passive"))
      (node (ref "T1") (pin "D") (pinfunction "D_D") (pintype "passive"))
      (node (ref "T9") (pin "3") (pinfunction "D_3") (pintype "passive"))
    )
    (net (code "56") (name "Net-(T10-D)") (class "Default")
      (node (ref "D1") (pin "A") (pinfunction "A_A") (pintype "passive"))
      (node (ref "T10") (pin "3") (pinfunction "D_3") (pintype "passive"))
      (node (ref "T2") (pin "D") (pinfunction "D_D") (pintype "passive"))
    )
    (net (code "57") (name "Net-(T11-D)") (class "Default")
      (node (ref "D4") (pin "A") (pinfunction "A_A") (pintype "passive"))
      (node (ref "T11") (pin "3") (pinfunction "D_3") (pintype "passive"))
      (node (ref "T3") (pin "D") (pinfunction "D_D") (pintype "passive"))
    )
    (net (code "58") (name "Net-(T12-D)") (class "Default")
      (node (ref "D3") (pin "A") (pinfunction "A_A") (pintype "passive"))
      (node (ref "T12") (pin "3") (pinfunction "D_3") (pintype "passive"))
      (node (ref "T4") (pin "D") (pinfunction "D_D") (pintype "passive"))
    )
    (net (code "59") (name "Net-(U1-AREF)") (class "Default")
      (node (ref "C27") (pin "1") (pinfunction "1_1") (pintype "passive"))
      (node (ref "U1") (pin "20") (pinfunction "AREF_20") (pintype "bidirectional"))
    )
    (net (code "60") (name "Net-(U1-PB6(XTAL1{slash}TOSC1))") (class "Default")
      (node (ref "C1") (pin "1") (pinfunction "1_1") (pintype "passive"))
      (node (ref "Q1") (pin "2") (pinfunction "2_2") (pintype "passive"))
      (node (ref "U1") (pin "7") (pinfunction "PB6(XTAL1/TOSC1)_7") (pintype "bidirectional"))
    )
    (net (code "61") (name "Net-(U1-PB7(XTAL2{slash}TOSC2))") (class "Default")
      (node (ref "C2") (pin "1") (pinfunction "1_1") (pintype "passive"))
      (node (ref "Q1") (pin "1") (pinfunction "1_1") (pintype "passive"))
      (node (ref "U1") (pin "8") (pinfunction "PB7(XTAL2/TOSC2)_8") (pintype "bidirectional"))
    )
    (net (code "62") (name "Net-(U2-IN+)") (class "Default")
      (node (ref "C11") (pin "1") (pinfunction "1_1") (pintype "passive"))
      (node (ref "R5") (pin "2") (pinfunction "2_2") (pintype "passive"))
      (node (ref "U2") (pin "4") (pinfunction "IN+_4") (pintype "input"))
    )
    (net (code "63") (name "Net-(U2-IN-)") (class "Default")
      (node (ref "C11") (pin "2") (pinfunction "2_2") (pintype "passive"))
      (node (ref "R6") (pin "2") (pinfunction "2_2") (pintype "passive"))
      (node (ref "U2") (pin "5") (pinfunction "IN-_5") (pintype "input"))
    )
    (net (code "64") (name "Net-(U3-IN+)") (class "Default")
      (node (ref "C12") (pin "1") (pinfunction "1_1") (pintype "passive"))
      (node (ref "R11") (pin "2") (pinfunction "2_2") (pintype "passive"))
      (node (ref "U3") (pin "4") (pinfunction "IN+_4") (pintype "input"))
    )
    (net (code "65") (name "Net-(U3-IN-)") (class "Default")
      (node (ref "C12") (pin "2") (pinfunction "2_2") (pintype "passive"))
      (node (ref "R10") (pin "2") (pinfunction "2_2") (pintype "passive"))
      (node (ref "U3") (pin "5") (pinfunction "IN-_5") (pintype "input"))
    )
    (net (code "66") (name "Net-(U4-G)") (class "Default")
      (node (ref "T5") (pin "G") (pinfunction "G_G") (pintype "passive"))
      (node (ref "U4") (pin "2") (pinfunction "G_2") (pintype "bidirectional"))
    )
    (net (code "67") (name "Net-(U8-IN+)") (class "Default")
      (node (ref "C8") (pin "1") (pinfunction "1_1") (pintype "passive"))
      (node (ref "R8") (pin "2") (pinfunction "2_2") (pintype "passive"))
      (node (ref "U8") (pin "4") (pinfunction "IN+_4") (pintype "input"))
    )
    (net (code "68") (name "Net-(U8-IN-)") (class "Default")
      (node (ref "C8") (pin "2") (pinfunction "2_2") (pintype "passive"))
      (node (ref "R22") (pin "2") (pinfunction "2_2") (pintype "passive"))
      (node (ref "U8") (pin "5") (pinfunction "IN-_5") (pintype "input"))
    )
    (net (code "69") (name "Net-(U9-IN+)") (class "Default")
      (node (ref "C7") (pin "1") (pinfunction "1_1") (pintype "passive"))
      (node (ref "R25") (pin "2") (pinfunction "2_2") (pintype "passive"))
      (node (ref "U9") (pin "4") (pinfunction "IN+_4") (pintype "input"))
    )
    (net (code "70") (name "Net-(U9-IN-)") (class "Default")
      (node (ref "C7") (pin "2") (pinfunction "2_2") (pintype "passive"))
      (node (ref "R24") (pin "2") (pinfunction "2_2") (pintype "passive"))
      (node (ref "U9") (pin "5") (pinfunction "IN-_5") (pintype "input"))
    )
    (net (code "71") (name "Net-(U10-G)") (class "Default")
      (node (ref "T6") (pin "G") (pinfunction "G_G") (pintype "passive"))
      (node (ref "U10") (pin "2") (pinfunction "G_2") (pintype "bidirectional"))
    )
    (net (code "72") (name "RESET") (class "Default")
      (node (ref "C22") (pin "2") (pinfunction "2_2") (pintype "passive"))
      (node (ref "ISP1") (pin "5") (pinfunction "RST_5") (pintype "output"))
      (node (ref "U1") (pin "29") (pinfunction "PC6(/RESET)_29") (pintype "bidirectional"))
    )
    (net (code "73") (name "RX") (class "Default")
      (node (ref "R16") (pin "2") (pinfunction "2_2") (pintype "passive"))
      (node (ref "U1") (pin "30") (pinfunction "PD0(RXD)_30") (pintype "bidirectional"))
    )
    (net (code "74") (name "SCK") (class "Default")
      (node (ref "ISP1") (pin "3") (pinfunction "SCK_3") (pintype "output"))
      (node (ref "U$7") (pin "16") (pinfunction "SCLK_16") (pintype "bidirectional"))
      (node (ref "U1") (pin "17") (pinfunction "PB5(SCK)_17") (pintype "bidirectional"))
    )
    (net (code "75") (name "TX") (class "Default")
      (node (ref "R18") (pin "2") (pinfunction "2_2") (pintype "passive"))
      (node (ref "U1") (pin "31") (pinfunction "PD1(TXD)_31") (pintype "bidirectional"))
    )
    (net (code "76") (name "T_BATT_1") (class "Default")
      (node (ref "H1") (pin "1") (pinfunction "MOUNT_1") (pintype "passive"))
      (node (ref "R31") (pin "2") (pinfunction "2_2") (pintype "passive"))
      (node (ref "U1") (pin "28") (pinfunction "PC5(ADC5/SCL)_28") (pintype "bidirectional"))
    )
    (net (code "77") (name "T_BATT_2") (class "Default")
      (node (ref "H2") (pin "1") (pinfunction "MOUNT_1") (pintype "passive"))
      (node (ref "R30") (pin "2") (pinfunction "2_2") (pintype "passive"))
      (node (ref "U1") (pin "27") (pinfunction "PC4(ADC4/SDA)_27") (pintype "bidirectional"))
    )
    (net (code "78") (name "T_BATT_3") (class "Default")
      (node (ref "H3") (pin "1") (pinfunction "MOUNT_1") (pintype "passive"))
      (node (ref "R29") (pin "2") (pinfunction "2_2") (pintype "passive"))
      (node (ref "U1") (pin "26") (pinfunction "PC3(ADC3)_26") (pintype "bidirectional"))
    )
    (net (code "79") (name "T_BATT_4") (class "Default")
      (node (ref "H4") (pin "1") (pinfunction "MOUNT_1") (pintype "passive"))
      (node (ref "R17") (pin "2") (pinfunction "2_2") (pintype "passive"))
      (node (ref "U1") (pin "25") (pinfunction "PC2(ADC2)_25") (pintype "bidirectional"))
    )
    (net (code "80") (name "USB_V_IN") (class "Default")
      (node (ref "F3") (pin "2") (pinfunction "2_2") (pintype "bidirectional"))
      (node (ref "X1") (pin "1") (pinfunction "1_1") (pintype "input"))
    )
    (net (code "81") (name "VCC") (class "Default")
      (node (ref "C15") (pin "1") (pinfunction "1_1") (pintype "passive"))
      (node (ref "C16") (pin "1") (pinfunction "1_1") (pintype "passive"))
      (node (ref "C17") (pin "1") (pinfunction "1_1") (pintype "passive"))
      (node (ref "C21") (pin "1") (pinfunction "1_1") (pintype "passive"))
      (node (ref "C23") (pin "1") (pinfunction "1_1") (pintype "passive"))
      (node (ref "C25") (pin "1") (pinfunction "1_1") (pintype "passive"))
      (node (ref "C26") (pin "1") (pinfunction "1_1") (pintype "passive"))
      (node (ref "C29") (pin "1") (pinfunction "1_1") (pintype "passive"))
      (node (ref "C3") (pin "1") (pinfunction "1_1") (pintype "passive"))
      (node (ref "C33") (pin "1") (pinfunction "1_1") (pintype "passive"))
      (node (ref "C5") (pin "1") (pinfunction "1_1") (pintype "passive"))
      (node (ref "C9") (pin "1") (pinfunction "1_1") (pintype "passive"))
      (node (ref "F3") (pin "1") (pinfunction "1_1") (pintype "bidirectional"))
      (node (ref "IC5") (pin "19") (pinfunction "RESET#_19") (pintype "input"))
      (node (ref "IC5") (pin "20") (pinfunction "VCC5I_20") (pintype "power_in"))
      (node (ref "IC5") (pin "4") (pinfunction "VCCIO_4") (pintype "power_in"))
      (node (ref "ISP1") (pin "2") (pinfunction "VCC_2") (pintype "power_in"))
      (node (ref "PC1") (pin "5") (pinfunction "V_IN_5") (pintype "bidirectional"))
      (node (ref "PC2") (pin "5") (pinfunction "V_IN_5") (pintype "bidirectional"))
      (node (ref "R1") (pin "1") (pinfunction "1_1") (pintype "passive"))
      (node (ref "R11") (pin "1") (pinfunction "1_1") (pintype "passive"))
      (node (ref "R12") (pin "1") (pinfunction "1_1") (pintype "passive"))
      (node (ref "R14") (pin "1") (pinfunction "1_1") (pintype "passive"))
      (node (ref "R20") (pin "2") (pinfunction "2_2") (pintype "passive"))
      (node (ref "R21") (pin "1") (pinfunction "1_1") (pintype "passive"))
      (node (ref "R25") (pin "1") (pinfunction "1_1") (pintype "passive"))
      (node (ref "R26") (pin "1") (pinfunction "1_1") (pintype "passive"))
      (node (ref "R3") (pin "2") (pinfunction "2_2") (pintype "passive"))
      (node (ref "R32") (pin "1") (pinfunction "1_1") (pintype "passive"))
      (node (ref "R33") (pin "1") (pinfunction "1_1") (pintype "passive"))
      (node (ref "R34") (pin "2") (pinfunction "2_2") (pintype "passive"))
      (node (ref "R35") (pin "1") (pinfunction "1_1") (pintype "passive"))
      (node (ref "R9") (pin "2") (pinfunction "2_2") (pintype "passive"))
      (node (ref "U$7") (pin "15") (pinfunction "DOUT_15") (pintype "bidirectional"))
      (node (ref "U1") (pin "4") (pinfunction "VCC_4") (pintype "bidirectional"))
      (node (ref "U1") (pin "6") (pinfunction "VCC_6") (pintype "bidirectional"))
      (node (ref "U2") (pin "3") (pinfunction "V+_3") (pintype "power_in"))
      (node (ref "U3") (pin "3") (pinfunction "V+_3") (pintype "power_in"))
      (node (ref "U5") (pin "2") (pinfunction "VO_2") (pintype "bidirectional"))
      (node (ref "U8") (pin "3") (pinfunction "V+_3") (pintype "power_in"))
      (node (ref "U9") (pin "3") (pinfunction "V+_3") (pintype "power_in"))
    )
    (net (code "82") (name "unconnected-(IC5-AVCC-NC-Pad24)") (class "Default")
      (node (ref "IC5") (pin "24") (pinfunction "AVCC-NC_24") (pintype "no_connect"))
    )
    (net (code "83") (name "unconnected-(IC5-CTS#-Pad11)") (class "Default")
      (node (ref "IC5") (pin "11") (pinfunction "CTS#_11") (pintype "input"))
    )
    (net (code "84") (name "unconnected-(IC5-DCD#-Pad10)") (class "Default")
      (node (ref "IC5") (pin "10") (pinfunction "DCD#_10") (pintype "input"))
    )
    (net (code "85") (name "unconnected-(IC5-DSR#-Pad9)") (class "Default")
      (node (ref "IC5") (pin "9") (pinfunction "DSR#_9") (pintype "input"))
    )
    (net (code "86") (name "unconnected-(IC5-GPIO2-Pad13)") (class "Default")
      (node (ref "IC5") (pin "13") (pinfunction "GPIO2_13") (pintype "output"))
    )
    (net (code "87") (name "unconnected-(IC5-GPIO3-Pad14)") (class "Default")
      (node (ref "IC5") (pin "14") (pinfunction "GPIO3_14") (pintype "input"))
    )
    (net (code "88") (name "unconnected-(IC5-OSCI-Pad27)") (class "Default")
      (node (ref "IC5") (pin "27") (pinfunction "OSCI_27") (pintype "input"))
    )
    (net (code "89") (name "unconnected-(IC5-OSCO-Pad28)") (class "Default")
      (node (ref "IC5") (pin "28") (pinfunction "OSCO_28") (pintype "output"))
    )
    (net (code "90") (name "unconnected-(IC5-RI#-Pad6)") (class "Default")
      (node (ref "IC5") (pin "6") (pinfunction "RI#_6") (pintype "input"))
    )
    (net (code "91") (name "unconnected-(IC5-RTS#-Pad3)") (class "Default")
      (node (ref "IC5") (pin "3") (pinfunction "RTS#_3") (pintype "output"))
    )
    (net (code "92") (name "unconnected-(IC5-SLEEP#-Pad12)") (class "Default")
      (node (ref "IC5") (pin "12") (pinfunction "SLEEP#_12") (pintype "input"))
    )
    (net (code "93") (name "unconnected-(IC5-VCC3I-NC-Pad8)") (class "Default")
      (node (ref "IC5") (pin "8") (pinfunction "VCC3I-NC_8") (pintype "no_connect"))
    )
    (net (code "94") (name "unconnected-(U$2-PadRING_SW)") (class "Default")
      (node (ref "U$2") (pin "RING_SW") (pinfunction "RING_SW_RING_SW") (pintype "bidirectional"))
    )
    (net (code "95") (name "unconnected-(U6-NC-Pad3)") (class "Default")
      (node (ref "U6") (pin "3") (pinfunction "NC_3") (pintype "no_connect"))
    )
    (net (code "96") (name "unconnected-(X1-Pad4)") (class "Default")
      (node (ref "X1") (pin "4") (pinfunction "4_4") (pintype "input"))
    )
  )
)
